# olm-flora-sqw-ds1340.net
KiCad netlist of a schematic drawn in EAGLE
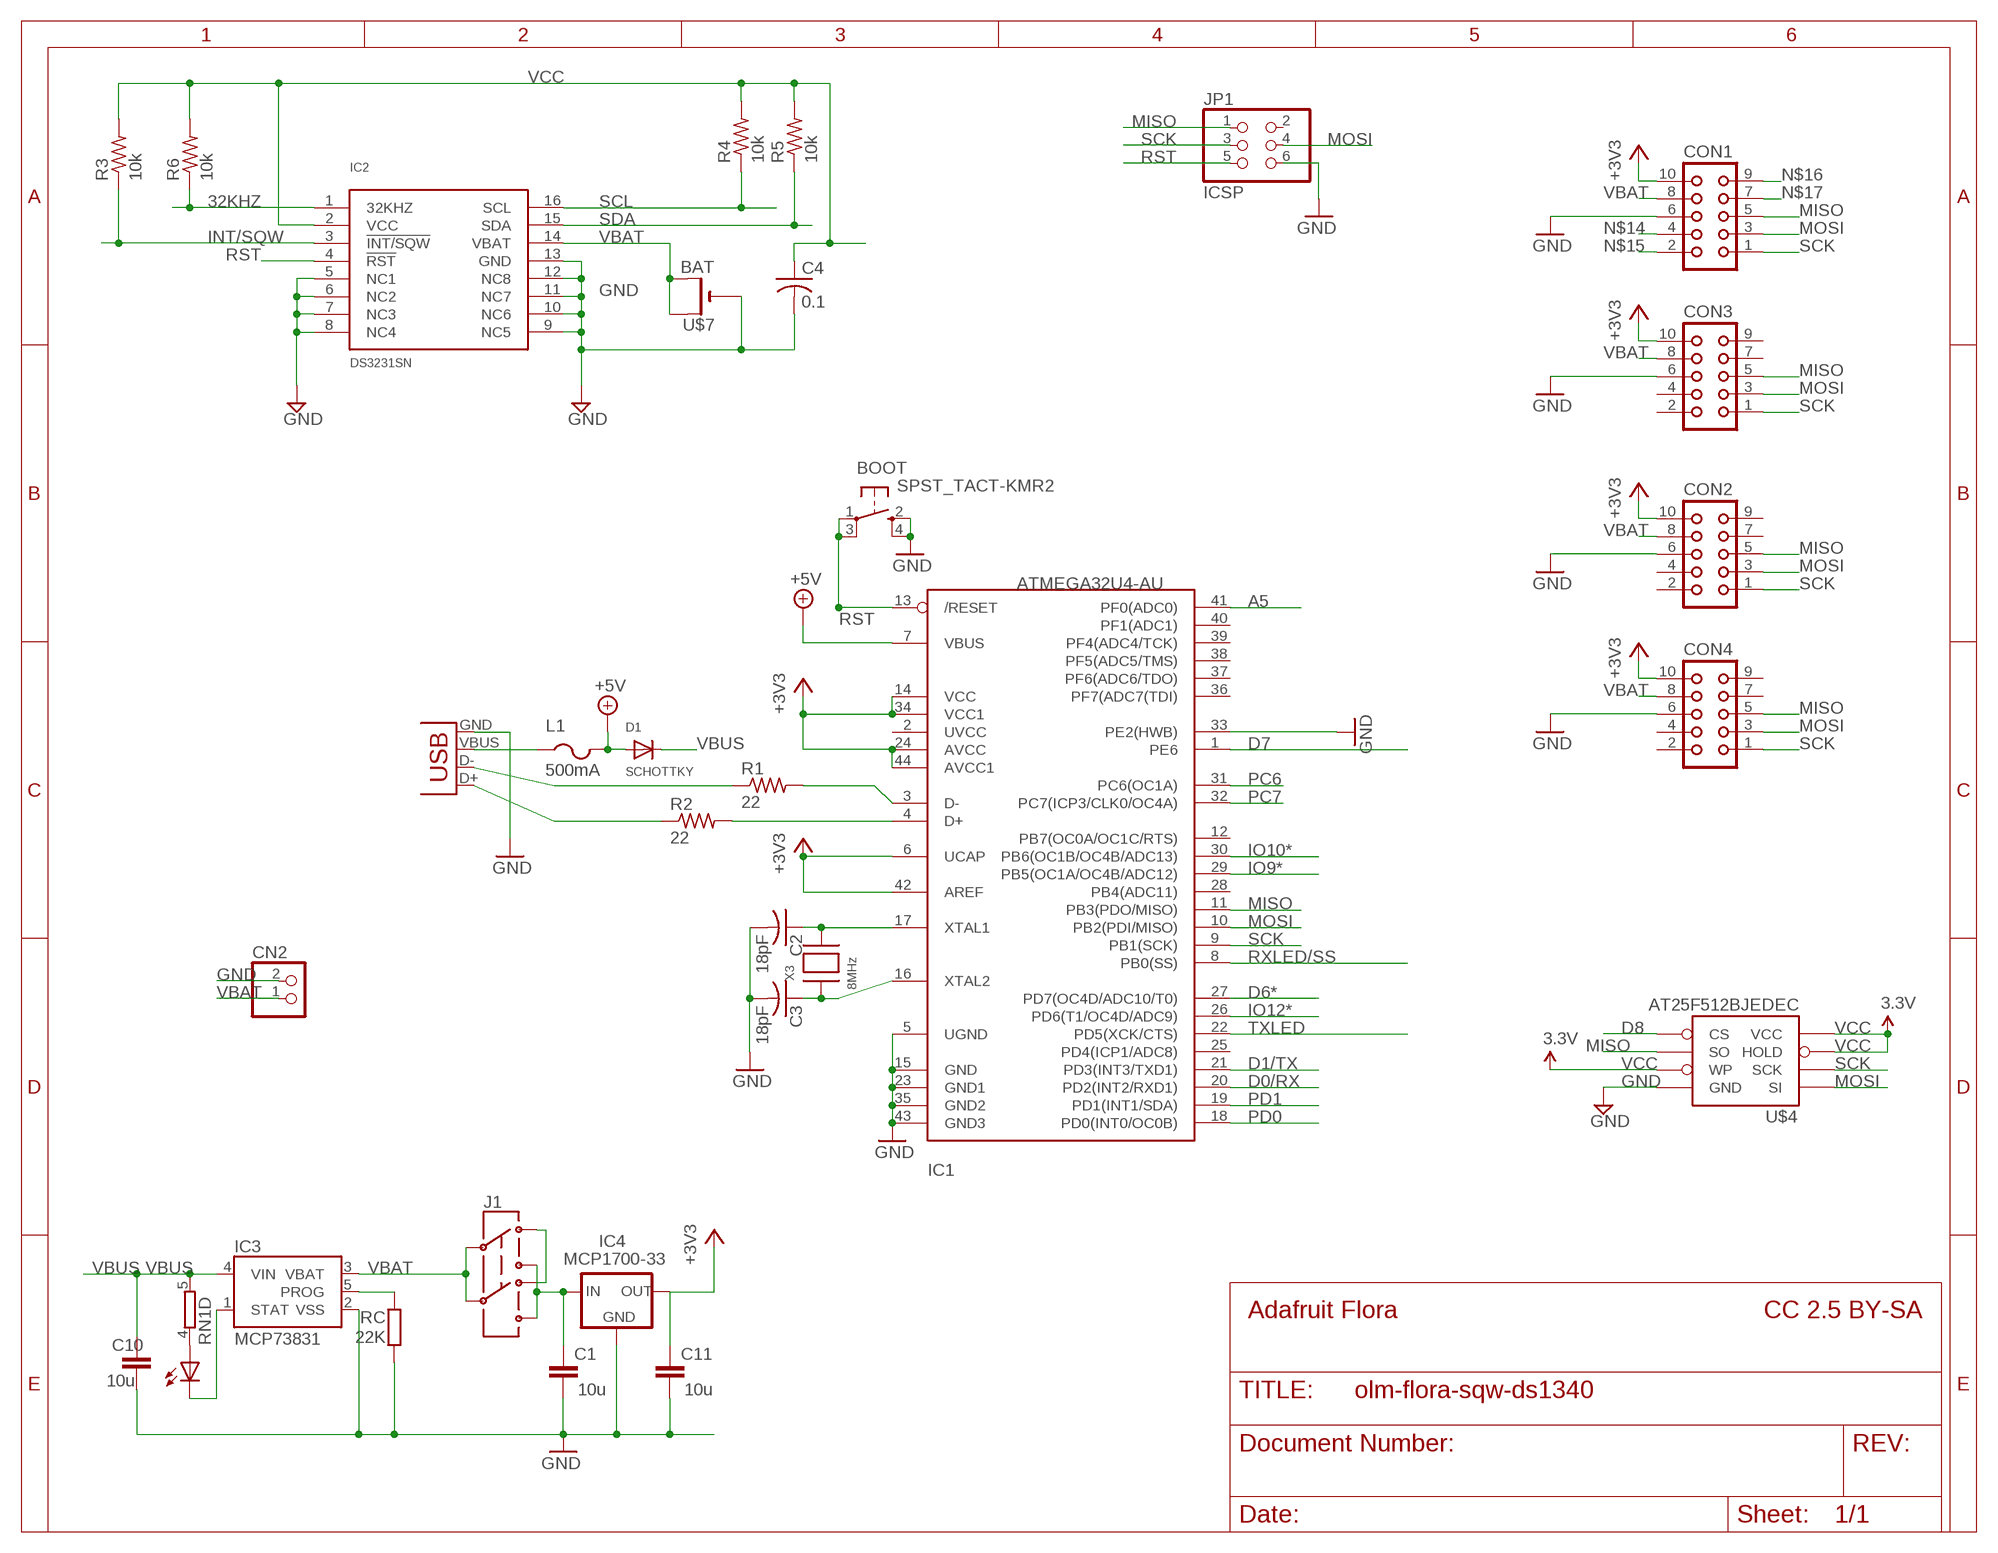
[diagram p0: schematic, sheet 1]

(export (version "E")
  (design (tool "Eeschema 10.0.6"))
  (components
    (comp (ref "BOOT")
      (value "SPST_TACT-KMR2")
      (footprint "eagle-import:KMR2")
      (libsource (lib "eagle-import") (part "SPST_TACT-KMR2"))
    )
    (comp (ref "C1")
      (value "10u")
      (footprint "eagle-import:C0805")
      (libsource (lib "eagle-import") (part "C-EUC0805"))
    )
    (comp (ref "C2")
      (value "18pF")
      (footprint "eagle-import:C0805K")
      (libsource (lib "eagle-import") (part "C-USC0805K"))
    )
    (comp (ref "C3")
      (value "18pF")
      (footprint "eagle-import:C0805K")
      (libsource (lib "eagle-import") (part "C-USC0805K"))
    )
    (comp (ref "C4")
      (value "0.1")
      (footprint "eagle-import:C0805K")
      (libsource (lib "eagle-import") (part "C-USC0805K"))
    )
    (comp (ref "C10")
      (value "10u")
      (footprint "eagle-import:C0805")
      (libsource (lib "eagle-import") (part "C-EUC0805"))
    )
    (comp (ref "C11")
      (value "10u")
      (footprint "eagle-import:C0805")
      (libsource (lib "eagle-import") (part "C-EUC0805"))
    )
    (comp (ref "CHG")
      (value "0805")
      (footprint "eagle-import:CHIPLED_0805")
      (libsource (lib "eagle-import") (part "LEDCHIPLED_0805"))
    )
    (comp (ref "CN2")
      (value "JST_2PIN-SMT-RA")
      (footprint "eagle-import:JST-PH-2-SMT-RA")
      (libsource (lib "eagle-import") (part "JST_2PIN-SMT-RA"))
    )
    (comp (ref "CON1")
      (value "CON10")
      (footprint "eagle-import:CON10")
      (libsource (lib "eagle-import") (part "CON10"))
    )
    (comp (ref "CON2")
      (value "CON10")
      (footprint "eagle-import:CON10")
      (libsource (lib "eagle-import") (part "CON10"))
    )
    (comp (ref "CON3")
      (value "CON10")
      (footprint "eagle-import:CON10")
      (libsource (lib "eagle-import") (part "CON10"))
    )
    (comp (ref "CON4")
      (value "CON10")
      (footprint "eagle-import:CON10")
      (libsource (lib "eagle-import") (part "CON10"))
    )
    (comp (ref "D1")
      (value "SCHOTTKY")
      (footprint "eagle-import:SOD-123")
      (libsource (lib "eagle-import") (part "DIODESOD-123"))
    )
    (comp (ref "IC1")
      (value "ATMEGA32U4-AU")
      (footprint "eagle-import:TQFP44")
      (libsource (lib "eagle-import") (part "ATMEGA32U4-AU"))
    )
    (comp (ref "IC2")
      (value "DS3231SN")
      (footprint "eagle-import:SO16W")
      (libsource (lib "eagle-import") (part "DS3231SN"))
    )
    (comp (ref "IC3")
      (value "MCP73831")
      (footprint "eagle-import:SOT23-5")
      (libsource (lib "eagle-import") (part "MCP73831"))
    )
    (comp (ref "IC4")
      (value "MCP1700-33")
      (footprint "eagle-import:SOT23")
      (libsource (lib "eagle-import") (part "MCP1700SOT233"))
    )
    (comp (ref "J1")
      (value "AYZ0202")
      (footprint "eagle-import:AYZ0202")
      (libsource (lib "eagle-import") (part "AYZ0202"))
    )
    (comp (ref "JP1")
      (value "ICSP")
      (footprint "eagle-import:2X03")
      (libsource (lib "eagle-import") (part "PINHD-2X3"))
    )
    (comp (ref "L1")
      (value "500mA")
      (footprint "eagle-import:R1206")
      (libsource (lib "eagle-import") (part "PTCFUSE-1206"))
    )
    (comp (ref "R1")
      (value "22")
      (footprint "eagle-import:R0805")
      (libsource (lib "eagle-import") (part "R-US_R0805"))
    )
    (comp (ref "R2")
      (value "22")
      (footprint "eagle-import:R0805")
      (libsource (lib "eagle-import") (part "R-US_R0805"))
    )
    (comp (ref "R3")
      (value "10k")
      (footprint "eagle-import:R0805")
      (libsource (lib "eagle-import") (part "R-US_R0805"))
    )
    (comp (ref "R4")
      (value "10k")
      (footprint "eagle-import:R0805")
      (libsource (lib "eagle-import") (part "R-US_R0805"))
    )
    (comp (ref "R5")
      (value "10k")
      (footprint "eagle-import:R0805")
      (libsource (lib "eagle-import") (part "R-US_R0805"))
    )
    (comp (ref "R6")
      (value "10k")
      (footprint "eagle-import:R0805")
      (libsource (lib "eagle-import") (part "R-US_R0805"))
    )
    (comp (ref "RC")
      (value "22K")
      (footprint "eagle-import:R0805")
      (libsource (lib "eagle-import") (part "R-EU_R0805"))
    )
    (comp (ref "RN1")
      (value "4R-NEXB38V")
      (footprint "eagle-import:EXB38V")
      (libsource (lib "eagle-import") (part "4R-NEXB38V"))
    )
    (comp (ref "U$4")
      (value "AT25F512BJEDEC")
      (footprint "eagle-import:SO08")
      (libsource (lib "eagle-import") (part "AT25F512BJEDEC"))
    )
    (comp (ref "U$7")
      (value "BAT")
      (footprint "eagle-import:CR1220-SMD")
      (libsource (lib "eagle-import") (part "CR1220SMT"))
    )
    (comp (ref "X1")
      (value "USBSMD")
      (footprint "eagle-import:USB-MINIB")
      (libsource (lib "eagle-import") (part "USBSMD"))
    )
    (comp (ref "X3")
      (value "8MHz")
      (footprint "eagle-import:NX5032")
      (libsource (lib "eagle-import") (part "XTALNX5032"))
    )
  )
  (nets
    (net (code "1") (name "+3V3") (class "Default")
      (node (ref "C11") (pin "1") (pinfunction "1_1") (pintype "passive"))
      (node (ref "CON1") (pin "10") (pinfunction "10_10") (pintype "passive"))
      (node (ref "CON2") (pin "10") (pinfunction "10_10") (pintype "passive"))
      (node (ref "CON3") (pin "10") (pinfunction "10_10") (pintype "passive"))
      (node (ref "CON4") (pin "10") (pinfunction "10_10") (pintype "passive"))
      (node (ref "IC1") (pin "14") (pinfunction "VCC_14") (pintype "bidirectional"))
      (node (ref "IC1") (pin "24") (pinfunction "AVCC_24") (pintype "bidirectional"))
      (node (ref "IC1") (pin "34") (pinfunction "VCC1_34") (pintype "bidirectional"))
      (node (ref "IC1") (pin "42") (pinfunction "AREF_42") (pintype "bidirectional"))
      (node (ref "IC1") (pin "44") (pinfunction "AVCC1_44") (pintype "bidirectional"))
      (node (ref "IC1") (pin "6") (pinfunction "UCAP_6") (pintype "bidirectional"))
      (node (ref "IC4") (pin "2") (pinfunction "OUT_2") (pintype "passive"))
    )
    (net (code "2") (name "+5V") (class "Default")
      (node (ref "D1") (pin "A") (pinfunction "A_A") (pintype "passive"))
      (node (ref "IC1") (pin "7") (pinfunction "VBUS_7") (pintype "bidirectional"))
      (node (ref "L1") (pin "2") (pinfunction "2_2") (pintype "passive"))
    )
    (net (code "3") (name "/32KHZ") (class "Default")
      (node (ref "IC2") (pin "1") (pinfunction "32KHZ_1") (pintype "bidirectional"))
      (node (ref "R6") (pin "1") (pinfunction "1_1") (pintype "passive"))
    )
    (net (code "4") (name "/A5") (class "Default")
      (node (ref "IC1") (pin "41") (pinfunction "PF0(ADC0)_41") (pintype "bidirectional"))
    )
    (net (code "5") (name "/D0{slash}RX") (class "Default")
      (node (ref "IC1") (pin "20") (pinfunction "PD2(INT2/RXD1)_20") (pintype "bidirectional"))
    )
    (net (code "6") (name "/D1{slash}TX") (class "Default")
      (node (ref "IC1") (pin "21") (pinfunction "PD3(INT3/TXD1)_21") (pintype "bidirectional"))
    )
    (net (code "7") (name "/D6*") (class "Default")
      (node (ref "IC1") (pin "27") (pinfunction "PD7(OC4D/ADC10/T0)_27") (pintype "bidirectional"))
    )
    (net (code "8") (name "/D7") (class "Default")
      (node (ref "IC1") (pin "1") (pinfunction "PE6_1") (pintype "bidirectional"))
    )
    (net (code "9") (name "/D8") (class "Default")
      (node (ref "U$4") (pin "1_CS") (pinfunction "CS_1_CS") (pintype "bidirectional"))
    )
    (net (code "10") (name "/INT{slash}SQW") (class "Default")
      (node (ref "IC2") (pin "3") (pinfunction "~{INT/SQW}_3") (pintype "bidirectional"))
      (node (ref "R3") (pin "1") (pinfunction "1_1") (pintype "passive"))
    )
    (net (code "11") (name "/IO9*") (class "Default")
      (node (ref "IC1") (pin "29") (pinfunction "PB5(OC1A/OC4B/ADC12)_29") (pintype "bidirectional"))
    )
    (net (code "12") (name "/IO10*") (class "Default")
      (node (ref "IC1") (pin "30") (pinfunction "PB6(OC1B/OC4B/ADC13)_30") (pintype "bidirectional"))
    )
    (net (code "13") (name "/IO12*") (class "Default")
      (node (ref "IC1") (pin "26") (pinfunction "PD6(T1/OC4D/ADC9)_26") (pintype "bidirectional"))
    )
    (net (code "14") (name "/MISO") (class "Default")
      (node (ref "CON1") (pin "5") (pinfunction "5_5") (pintype "passive"))
      (node (ref "CON2") (pin "5") (pinfunction "5_5") (pintype "passive"))
      (node (ref "CON3") (pin "5") (pinfunction "5_5") (pintype "passive"))
      (node (ref "CON4") (pin "5") (pinfunction "5_5") (pintype "passive"))
      (node (ref "IC1") (pin "11") (pinfunction "PB3(PDO/MISO)_11") (pintype "bidirectional"))
      (node (ref "JP1") (pin "1") (pinfunction "1_1") (pintype "passive"))
      (node (ref "U$4") (pin "2_SO") (pinfunction "SO_2_SO") (pintype "bidirectional"))
    )
    (net (code "15") (name "/MOSI") (class "Default")
      (node (ref "CON1") (pin "3") (pinfunction "3_3") (pintype "passive"))
      (node (ref "CON2") (pin "3") (pinfunction "3_3") (pintype "passive"))
      (node (ref "CON3") (pin "3") (pinfunction "3_3") (pintype "passive"))
      (node (ref "CON4") (pin "3") (pinfunction "3_3") (pintype "passive"))
      (node (ref "IC1") (pin "10") (pinfunction "PB2(PDI/MISO)_10") (pintype "bidirectional"))
      (node (ref "JP1") (pin "4") (pinfunction "4_4") (pintype "passive"))
      (node (ref "U$4") (pin "5_SI") (pinfunction "SI_5_SI") (pintype "bidirectional"))
    )
    (net (code "16") (name "/N$14") (class "Default")
      (node (ref "CON1") (pin "4") (pinfunction "4_4") (pintype "passive"))
    )
    (net (code "17") (name "/N$15") (class "Default")
      (node (ref "CON1") (pin "2") (pinfunction "2_2") (pintype "passive"))
    )
    (net (code "18") (name "/N$16") (class "Default")
      (node (ref "CON1") (pin "9") (pinfunction "9_9") (pintype "passive"))
    )
    (net (code "19") (name "/N$17") (class "Default")
      (node (ref "CON1") (pin "7") (pinfunction "7_7") (pintype "passive"))
    )
    (net (code "20") (name "/PC6") (class "Default")
      (node (ref "IC1") (pin "31") (pinfunction "PC6(OC1A)_31") (pintype "bidirectional"))
    )
    (net (code "21") (name "/PC7") (class "Default")
      (node (ref "IC1") (pin "32") (pinfunction "PC7(ICP3/CLK0/OC4A)_32") (pintype "bidirectional"))
    )
    (net (code "22") (name "/PD0") (class "Default")
      (node (ref "IC1") (pin "18") (pinfunction "PD0(INT0/OC0B)_18") (pintype "bidirectional"))
    )
    (net (code "23") (name "/PD1") (class "Default")
      (node (ref "IC1") (pin "19") (pinfunction "PD1(INT1/SDA)_19") (pintype "bidirectional"))
    )
    (net (code "24") (name "/RST") (class "Default")
      (node (ref "BOOT") (pin "1") (pinfunction "P_1") (pintype "passive"))
      (node (ref "BOOT") (pin "3") (pinfunction "P1_3") (pintype "passive"))
      (node (ref "IC1") (pin "13") (pinfunction "/RESET_13") (pintype "bidirectional"))
      (node (ref "IC2") (pin "4") (pinfunction "~{RST}_4") (pintype "bidirectional"))
      (node (ref "JP1") (pin "5") (pinfunction "5_5") (pintype "passive"))
    )
    (net (code "25") (name "/RXLED{slash}SS") (class "Default")
      (node (ref "IC1") (pin "8") (pinfunction "PB0(SS)_8") (pintype "bidirectional"))
    )
    (net (code "26") (name "/SCK") (class "Default")
      (node (ref "CON1") (pin "1") (pinfunction "1_1") (pintype "passive"))
      (node (ref "CON2") (pin "1") (pinfunction "1_1") (pintype "passive"))
      (node (ref "CON3") (pin "1") (pinfunction "1_1") (pintype "passive"))
      (node (ref "CON4") (pin "1") (pinfunction "1_1") (pintype "passive"))
      (node (ref "IC1") (pin "9") (pinfunction "PB1(SCK)_9") (pintype "bidirectional"))
      (node (ref "JP1") (pin "3") (pinfunction "3_3") (pintype "passive"))
      (node (ref "U$4") (pin "6_SCK") (pinfunction "SCK_6_SCK") (pintype "bidirectional"))
    )
    (net (code "27") (name "/SCL") (class "Default")
      (node (ref "IC2") (pin "16") (pinfunction "SCL_16") (pintype "bidirectional"))
      (node (ref "R4") (pin "1") (pinfunction "1_1") (pintype "passive"))
    )
    (net (code "28") (name "/SDA") (class "Default")
      (node (ref "IC2") (pin "15") (pinfunction "SDA_15") (pintype "bidirectional"))
      (node (ref "R5") (pin "1") (pinfunction "1_1") (pintype "passive"))
    )
    (net (code "29") (name "/TXLED") (class "Default")
      (node (ref "IC1") (pin "22") (pinfunction "PD5(XCK/CTS)_22") (pintype "bidirectional"))
    )
    (net (code "30") (name "/VBAT") (class "Default")
      (node (ref "CN2") (pin "1") (pinfunction "2_1") (pintype "passive"))
      (node (ref "CON1") (pin "8") (pinfunction "8_8") (pintype "passive"))
      (node (ref "CON2") (pin "8") (pinfunction "8_8") (pintype "passive"))
      (node (ref "CON3") (pin "8") (pinfunction "8_8") (pintype "passive"))
      (node (ref "CON4") (pin "8") (pinfunction "8_8") (pintype "passive"))
      (node (ref "IC2") (pin "14") (pinfunction "VBAT_14") (pintype "bidirectional"))
      (node (ref "IC3") (pin "3") (pinfunction "VBAT_3") (pintype "power_in"))
      (node (ref "J1") (pin "2") (pinfunction "2_2") (pintype "bidirectional"))
      (node (ref "J1") (pin "5") (pinfunction "5_5") (pintype "bidirectional"))
      (node (ref "U$7") (pin "+$1") (pinfunction "+_+$1") (pintype "passive"))
      (node (ref "U$7") (pin "+$2") (pinfunction "+1_+$2") (pintype "passive"))
    )
    (net (code "31") (name "/VBUS") (class "Default")
      (node (ref "C10") (pin "1") (pinfunction "1_1") (pintype "passive"))
      (node (ref "D1") (pin "C") (pinfunction "C_C") (pintype "passive"))
      (node (ref "IC3") (pin "4") (pinfunction "VIN_4") (pintype "power_in"))
      (node (ref "L1") (pin "1") (pinfunction "1_1") (pintype "passive"))
      (node (ref "RN1") (pin "5") (pinfunction "2_5") (pintype "passive"))
      (node (ref "X1") (pin "VBUS") (pinfunction "VBUS_VBUS") (pintype "bidirectional"))
    )
    (net (code "32") (name "3.3V") (class "Default")
      (node (ref "C4") (pin "1") (pinfunction "1_1") (pintype "passive"))
      (node (ref "IC2") (pin "2") (pinfunction "VCC_2") (pintype "bidirectional"))
      (node (ref "R3") (pin "2") (pinfunction "2_2") (pintype "passive"))
      (node (ref "R4") (pin "2") (pinfunction "2_2") (pintype "passive"))
      (node (ref "R5") (pin "2") (pinfunction "2_2") (pintype "passive"))
      (node (ref "R6") (pin "2") (pinfunction "2_2") (pintype "passive"))
      (node (ref "U$4") (pin "3_WP") (pinfunction "WP_3_WP") (pintype "bidirectional"))
      (node (ref "U$4") (pin "7_HOLD") (pinfunction "HOLD_7_HOLD") (pintype "bidirectional"))
      (node (ref "U$4") (pin "8_VCC") (pinfunction "VCC_8_VCC") (pintype "bidirectional"))
    )
    (net (code "33") (name "GND") (class "Default")
      (node (ref "BOOT") (pin "2") (pinfunction "S_2") (pintype "passive"))
      (node (ref "BOOT") (pin "4") (pinfunction "S1_4") (pintype "passive"))
      (node (ref "C1") (pin "2") (pinfunction "2_2") (pintype "passive"))
      (node (ref "C10") (pin "2") (pinfunction "2_2") (pintype "passive"))
      (node (ref "C11") (pin "2") (pinfunction "2_2") (pintype "passive"))
      (node (ref "C2") (pin "2") (pinfunction "2_2") (pintype "passive"))
      (node (ref "C3") (pin "2") (pinfunction "2_2") (pintype "passive"))
      (node (ref "C4") (pin "2") (pinfunction "2_2") (pintype "passive"))
      (node (ref "CN2") (pin "2") (pinfunction "1_2") (pintype "passive"))
      (node (ref "CON1") (pin "6") (pinfunction "6_6") (pintype "passive"))
      (node (ref "CON2") (pin "6") (pinfunction "6_6") (pintype "passive"))
      (node (ref "CON3") (pin "6") (pinfunction "6_6") (pintype "passive"))
      (node (ref "CON4") (pin "6") (pinfunction "6_6") (pintype "passive"))
      (node (ref "IC1") (pin "15") (pinfunction "GND_15") (pintype "bidirectional"))
      (node (ref "IC1") (pin "23") (pinfunction "GND1_23") (pintype "bidirectional"))
      (node (ref "IC1") (pin "33") (pinfunction "PE2(HWB)_33") (pintype "bidirectional"))
      (node (ref "IC1") (pin "35") (pinfunction "GND2_35") (pintype "bidirectional"))
      (node (ref "IC1") (pin "43") (pinfunction "GND3_43") (pintype "bidirectional"))
      (node (ref "IC1") (pin "5") (pinfunction "UGND_5") (pintype "bidirectional"))
      (node (ref "IC2") (pin "10") (pinfunction "NC6_10") (pintype "bidirectional"))
      (node (ref "IC2") (pin "11") (pinfunction "NC7_11") (pintype "bidirectional"))
      (node (ref "IC2") (pin "12") (pinfunction "NC8_12") (pintype "bidirectional"))
      (node (ref "IC2") (pin "13") (pinfunction "GND_13") (pintype "bidirectional"))
      (node (ref "IC2") (pin "5") (pinfunction "NC1_5") (pintype "bidirectional"))
      (node (ref "IC2") (pin "6") (pinfunction "NC2_6") (pintype "bidirectional"))
      (node (ref "IC2") (pin "7") (pinfunction "NC3_7") (pintype "bidirectional"))
      (node (ref "IC2") (pin "8") (pinfunction "NC4_8") (pintype "bidirectional"))
      (node (ref "IC2") (pin "9") (pinfunction "NC5_9") (pintype "bidirectional"))
      (node (ref "IC3") (pin "2") (pinfunction "VSS_2") (pintype "power_in"))
      (node (ref "IC4") (pin "1") (pinfunction "GND_1") (pintype "input"))
      (node (ref "JP1") (pin "6") (pinfunction "6_6") (pintype "passive"))
      (node (ref "RC") (pin "1") (pinfunction "1_1") (pintype "passive"))
      (node (ref "U$4") (pin "4_GND") (pinfunction "GND_4_GND") (pintype "bidirectional"))
      (node (ref "U$7") (pin "-") (pinfunction "-_-") (pintype "passive"))
      (node (ref "X1") (pin "GND") (pinfunction "GND_GND") (pintype "bidirectional"))
    )
    (net (code "34") (name "Net-(IC1-D+)") (class "Default")
      (node (ref "IC1") (pin "4") (pinfunction "D+_4") (pintype "bidirectional"))
      (node (ref "R2") (pin "2") (pinfunction "2_2") (pintype "passive"))
    )
    (net (code "35") (name "Net-(IC1-D-)") (class "Default")
      (node (ref "IC1") (pin "3") (pinfunction "D-_3") (pintype "bidirectional"))
      (node (ref "R1") (pin "2") (pinfunction "2_2") (pintype "passive"))
    )
    (net (code "36") (name "Net-(IC1-XTAL1)") (class "Default")
      (node (ref "C2") (pin "1") (pinfunction "1_1") (pintype "passive"))
      (node (ref "IC1") (pin "17") (pinfunction "XTAL1_17") (pintype "bidirectional"))
      (node (ref "X3") (pin "P$2") (pinfunction "P$2_P$2") (pintype "bidirectional"))
    )
    (net (code "37") (name "Net-(IC1-XTAL2)") (class "Default")
      (node (ref "C3") (pin "1") (pinfunction "1_1") (pintype "passive"))
      (node (ref "IC1") (pin "16") (pinfunction "XTAL2_16") (pintype "bidirectional"))
      (node (ref "X3") (pin "P$1") (pinfunction "P$1_P$1") (pintype "bidirectional"))
    )
    (net (code "38") (name "Net-(IC3-PROG)") (class "Default")
      (node (ref "IC3") (pin "5") (pinfunction "PROG_5") (pintype "input"))
      (node (ref "RC") (pin "2") (pinfunction "2_2") (pintype "passive"))
    )
    (net (code "39") (name "Net-(IC3-STAT)") (class "Default")
      (node (ref "CHG") (pin "C") (pinfunction "C_C") (pintype "passive"))
      (node (ref "IC3") (pin "1") (pinfunction "STAT_1") (pintype "output"))
    )
    (net (code "40") (name "Net-(IC4-IN)") (class "Default")
      (node (ref "C1") (pin "1") (pinfunction "1_1") (pintype "passive"))
      (node (ref "IC4") (pin "3") (pinfunction "IN_3") (pintype "input"))
      (node (ref "J1") (pin "1") (pinfunction "3_1") (pintype "bidirectional"))
      (node (ref "J1") (pin "4") (pinfunction "6_4") (pintype "bidirectional"))
    )
    (net (code "41") (name "Net-(J1-1)") (class "Default")
      (node (ref "J1") (pin "3") (pinfunction "1_3") (pintype "bidirectional"))
      (node (ref "J1") (pin "6") (pinfunction "4_6") (pintype "bidirectional"))
    )
    (net (code "42") (name "Net-(R1-Pad1)") (class "Default")
      (node (ref "R1") (pin "1") (pinfunction "1_1") (pintype "passive"))
      (node (ref "X1") (pin "D-") (pinfunction "D-_D-") (pintype "bidirectional"))
    )
    (net (code "43") (name "Net-(R2-Pad1)") (class "Default")
      (node (ref "R2") (pin "1") (pinfunction "1_1") (pintype "passive"))
      (node (ref "X1") (pin "D+") (pinfunction "D+_D+") (pintype "bidirectional"))
    )
    (net (code "44") (name "Net-(RN1D-1)") (class "Default")
      (node (ref "CHG") (pin "A") (pinfunction "A_A") (pintype "passive"))
      (node (ref "RN1") (pin "4") (pinfunction "1_4") (pintype "passive"))
    )
    (net (code "45") (name "unconnected-(CON2-Pad2)") (class "Default")
      (node (ref "CON2") (pin "2") (pinfunction "2_2") (pintype "passive"))
    )
    (net (code "46") (name "unconnected-(CON2-Pad4)") (class "Default")
      (node (ref "CON2") (pin "4") (pinfunction "4_4") (pintype "passive"))
    )
    (net (code "47") (name "unconnected-(CON2-Pad7)") (class "Default")
      (node (ref "CON2") (pin "7") (pinfunction "7_7") (pintype "passive"))
    )
    (net (code "48") (name "unconnected-(CON2-Pad9)") (class "Default")
      (node (ref "CON2") (pin "9") (pinfunction "9_9") (pintype "passive"))
    )
    (net (code "49") (name "unconnected-(CON3-Pad2)") (class "Default")
      (node (ref "CON3") (pin "2") (pinfunction "2_2") (pintype "passive"))
    )
    (net (code "50") (name "unconnected-(CON3-Pad4)") (class "Default")
      (node (ref "CON3") (pin "4") (pinfunction "4_4") (pintype "passive"))
    )
    (net (code "51") (name "unconnected-(CON3-Pad7)") (class "Default")
      (node (ref "CON3") (pin "7") (pinfunction "7_7") (pintype "passive"))
    )
    (net (code "52") (name "unconnected-(CON3-Pad9)") (class "Default")
      (node (ref "CON3") (pin "9") (pinfunction "9_9") (pintype "passive"))
    )
    (net (code "53") (name "unconnected-(CON4-Pad2)") (class "Default")
      (node (ref "CON4") (pin "2") (pinfunction "2_2") (pintype "passive"))
    )
    (net (code "54") (name "unconnected-(CON4-Pad4)") (class "Default")
      (node (ref "CON4") (pin "4") (pinfunction "4_4") (pintype "passive"))
    )
    (net (code "55") (name "unconnected-(CON4-Pad7)") (class "Default")
      (node (ref "CON4") (pin "7") (pinfunction "7_7") (pintype "passive"))
    )
    (net (code "56") (name "unconnected-(CON4-Pad9)") (class "Default")
      (node (ref "CON4") (pin "9") (pinfunction "9_9") (pintype "passive"))
    )
    (net (code "57") (name "unconnected-(IC1-PB4(ADC11)-Pad28)") (class "Default")
      (node (ref "IC1") (pin "28") (pinfunction "PB4(ADC11)_28") (pintype "bidirectional"))
    )
    (net (code "58") (name "unconnected-(IC1-PB7(OC0A{slash}OC1C{slash}RTS)-Pad12)") (class "Default")
      (node (ref "IC1") (pin "12") (pinfunction "PB7(OC0A/OC1C/RTS)_12") (pintype "bidirectional"))
    )
    (net (code "59") (name "unconnected-(IC1-PD4(ICP1{slash}ADC8)-Pad25)") (class "Default")
      (node (ref "IC1") (pin "25") (pinfunction "PD4(ICP1/ADC8)_25") (pintype "bidirectional"))
    )
    (net (code "60") (name "unconnected-(IC1-PF1(ADC1)-Pad40)") (class "Default")
      (node (ref "IC1") (pin "40") (pinfunction "PF1(ADC1)_40") (pintype "bidirectional"))
    )
    (net (code "61") (name "unconnected-(IC1-PF4(ADC4{slash}TCK)-Pad39)") (class "Default")
      (node (ref "IC1") (pin "39") (pinfunction "PF4(ADC4/TCK)_39") (pintype "bidirectional"))
    )
    (net (code "62") (name "unconnected-(IC1-PF5(ADC5{slash}TMS)-Pad38)") (class "Default")
      (node (ref "IC1") (pin "38") (pinfunction "PF5(ADC5/TMS)_38") (pintype "bidirectional"))
    )
    (net (code "63") (name "unconnected-(IC1-PF6(ADC6{slash}TDO)-Pad37)") (class "Default")
      (node (ref "IC1") (pin "37") (pinfunction "PF6(ADC6/TDO)_37") (pintype "bidirectional"))
    )
    (net (code "64") (name "unconnected-(IC1-PF7(ADC7(TDI)-Pad36)") (class "Default")
      (node (ref "IC1") (pin "36") (pinfunction "PF7(ADC7(TDI)_36") (pintype "bidirectional"))
    )
    (net (code "65") (name "unconnected-(IC1-UVCC-Pad2)") (class "Default")
      (node (ref "IC1") (pin "2") (pinfunction "UVCC_2") (pintype "bidirectional"))
    )
    (net (code "66") (name "unconnected-(JP1-Pad2)") (class "Default")
      (node (ref "JP1") (pin "2") (pinfunction "2_2") (pintype "passive"))
    )
  )
)
